# tritiled2x_programmer.net
KiCad netlist of a schematic drawn in EAGLE
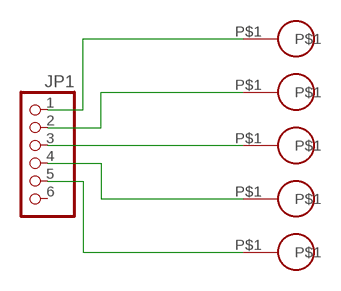
[diagram p0: schematic, sheet 1]

(export (version "E")
  (design (tool "Eeschema 10.0.6"))
  (components
    (comp (ref "JP1")
      (value "PINHD-1X6")
      (footprint "eagle-import:1X06")
      (libsource (lib "eagle-import") (part "PINHD-1X6"))
    )
    (comp (ref "U$1")
      (value "SPRING_PIN")
      (footprint "eagle-import:SPRING_PIN")
      (libsource (lib "eagle-import") (part "SPRING_PIN"))
    )
    (comp (ref "U$2")
      (value "SPRING_PIN")
      (footprint "eagle-import:SPRING_PIN")
      (libsource (lib "eagle-import") (part "SPRING_PIN"))
    )
    (comp (ref "U$3")
      (value "SPRING_PIN")
      (footprint "eagle-import:SPRING_PIN")
      (libsource (lib "eagle-import") (part "SPRING_PIN"))
    )
    (comp (ref "U$4")
      (value "SPRING_PIN")
      (footprint "eagle-import:SPRING_PIN")
      (libsource (lib "eagle-import") (part "SPRING_PIN"))
    )
    (comp (ref "U$5")
      (value "SPRING_PIN")
      (footprint "eagle-import:SPRING_PIN")
      (libsource (lib "eagle-import") (part "SPRING_PIN"))
    )
  )
  (nets
    (net (code "1") (name "Net-(JP1-Pad1)") (class "Default")
      (node (ref "JP1") (pin "1") (pinfunction "1_1") (pintype "passive"))
      (node (ref "U$1") (pin "P$1") (pinfunction "P$1_P$1") (pintype "bidirectional"))
    )
    (net (code "2") (name "Net-(JP1-Pad2)") (class "Default")
      (node (ref "JP1") (pin "2") (pinfunction "2_2") (pintype "passive"))
      (node (ref "U$2") (pin "P$1") (pinfunction "P$1_P$1") (pintype "bidirectional"))
    )
    (net (code "3") (name "Net-(JP1-Pad3)") (class "Default")
      (node (ref "JP1") (pin "3") (pinfunction "3_3") (pintype "passive"))
      (node (ref "U$3") (pin "P$1") (pinfunction "P$1_P$1") (pintype "bidirectional"))
    )
    (net (code "4") (name "Net-(JP1-Pad4)") (class "Default")
      (node (ref "JP1") (pin "4") (pinfunction "4_4") (pintype "passive"))
      (node (ref "U$4") (pin "P$1") (pinfunction "P$1_P$1") (pintype "bidirectional"))
    )
    (net (code "5") (name "Net-(JP1-Pad5)") (class "Default")
      (node (ref "JP1") (pin "5") (pinfunction "5_5") (pintype "passive"))
      (node (ref "U$5") (pin "P$1") (pinfunction "P$1_P$1") (pintype "bidirectional"))
    )
    (net (code "6") (name "unconnected-(JP1-Pad6)") (class "Default")
      (node (ref "JP1") (pin "6") (pinfunction "6_6") (pintype "passive"))
    )
  )
)
